# PDB_first.net
KiCad netlist of a schematic drawn in Altium Designer
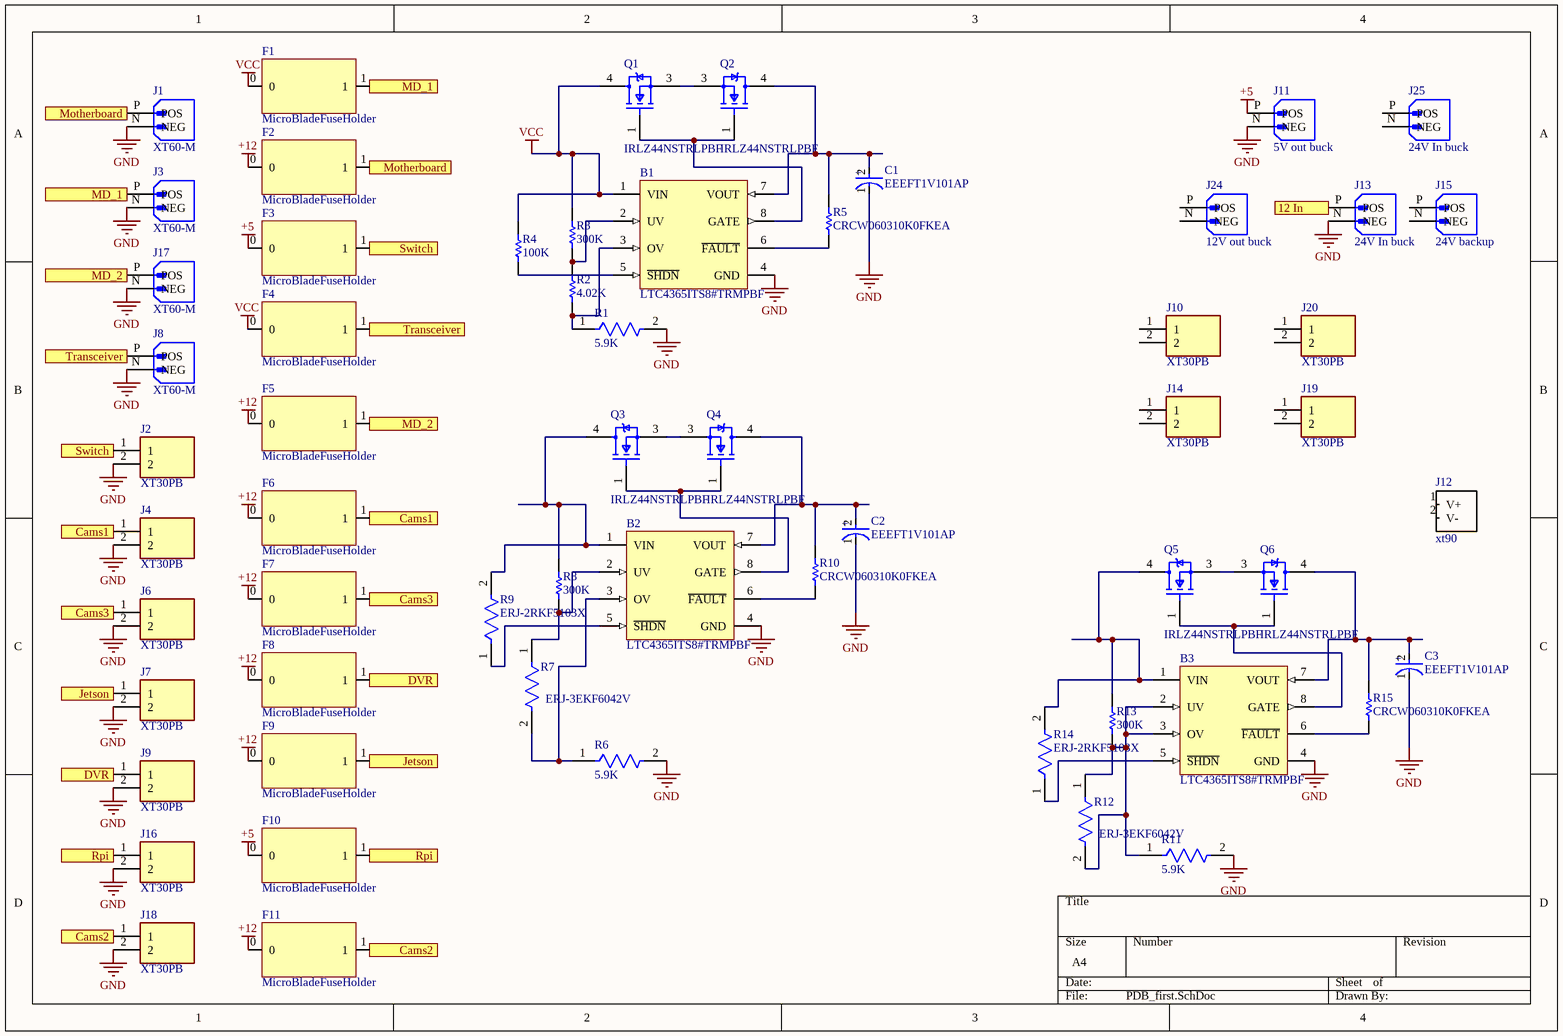
[diagram p0: PDB_first.SchDoc]

(export (version "E")
  (design (tool "Eeschema 10.0.6"))
  (components
    (comp (ref "B1")
      (value "LTC4365ITS8#TRMPBF")
      (footprint "LT-TS8-8-TSOT-23_V")
      (fields (field (name "MANUFACTURER") "Linear Technology"))
      (libsource (lib "Altium Content Vault") (part "LT-LTC4365-TS8-8"))
    )
    (comp (ref "B2")
      (value "LTC4365ITS8#TRMPBF")
      (footprint "LT-TS8-8-TSOT-23_V")
      (fields (field (name "MANUFACTURER") "Linear Technology"))
      (libsource (lib "Altium Content Vault") (part "LT-LTC4365-TS8-8"))
    )
    (comp (ref "B3")
      (value "LTC4365ITS8#TRMPBF")
      (footprint "LT-TS8-8-TSOT-23_V")
      (fields (field (name "MANUFACTURER") "Linear Technology"))
      (libsource (lib "Altium Content Vault") (part "LT-LTC4365-TS8-8"))
    )
    (comp (ref "C1")
      (value "EEEFT1V101AP")
      (footprint "FP-FTD-MFG")
      (description "CAP ALUM 100UF 20% 35V SMD")
      (fields (field (name "VOLTAGE") "35V") (field (name "TOLERANCE") "20%"))
      (libsource (lib "Altium Content Vault") (part "a00bbbee19879c290e62620ae7e47b1"))
    )
    (comp (ref "C2")
      (value "EEEFT1V101AP")
      (footprint "FP-FTD-MFG")
      (description "CAP ALUM 100UF 20% 35V SMD")
      (fields (field (name "VOLTAGE") "35V") (field (name "TOLERANCE") "20%"))
      (libsource (lib "Altium Content Vault") (part "a00bbbee19879c290e62620ae7e47b1"))
    )
    (comp (ref "C3")
      (value "EEEFT1V101AP")
      (footprint "FP-FTD-MFG")
      (description "CAP ALUM 100UF 20% 35V SMD")
      (fields (field (name "VOLTAGE") "35V") (field (name "TOLERANCE") "20%"))
      (libsource (lib "Altium Content Vault") (part "a00bbbee19879c290e62620ae7e47b1"))
    )
    (comp (ref "F1")
      (value "MicroBladeFuseHolder")
      (libsource (lib "MicroBladeFuse") (part "MicroBladeFuseHolder"))
    )
    (comp (ref "F2")
      (value "MicroBladeFuseHolder")
      (libsource (lib "MicroBladeFuse") (part "MicroBladeFuseHolder"))
    )
    (comp (ref "F3")
      (value "MicroBladeFuseHolder")
      (libsource (lib "MicroBladeFuse") (part "MicroBladeFuseHolder"))
    )
    (comp (ref "F4")
      (value "MicroBladeFuseHolder")
      (libsource (lib "MicroBladeFuse") (part "MicroBladeFuseHolder"))
    )
    (comp (ref "F5")
      (value "MicroBladeFuseHolder")
      (libsource (lib "MicroBladeFuse") (part "MicroBladeFuseHolder"))
    )
    (comp (ref "F6")
      (value "MicroBladeFuseHolder")
      (libsource (lib "MicroBladeFuse") (part "MicroBladeFuseHolder"))
    )
    (comp (ref "F7")
      (value "MicroBladeFuseHolder")
      (libsource (lib "MicroBladeFuse") (part "MicroBladeFuseHolder"))
    )
    (comp (ref "F8")
      (value "MicroBladeFuseHolder")
      (libsource (lib "MicroBladeFuse") (part "MicroBladeFuseHolder"))
    )
    (comp (ref "F9")
      (value "MicroBladeFuseHolder")
      (libsource (lib "MicroBladeFuse") (part "MicroBladeFuseHolder"))
    )
    (comp (ref "F10")
      (value "MicroBladeFuseHolder")
      (libsource (lib "MicroBladeFuse") (part "MicroBladeFuseHolder"))
    )
    (comp (ref "F11")
      (value "MicroBladeFuseHolder")
      (libsource (lib "MicroBladeFuse") (part "MicroBladeFuseHolder"))
    )
    (comp (ref "J1")
      (value "XT60-M")
      (footprint "AMASS_XT60-M")
      (description "Plug; DC supply; XT60; male; PIN: 2; for cable; soldered; 30A; 500V")
      (fields (field (name "MF") "AMASS"))
      (libsource (lib "XT60-M") (part "XT60-M"))
    )
    (comp (ref "J2")
      (value "XT30PB")
      (footprint "SamacSys:XT30PB")
      (description "Connector")
      (libsource (lib "SamacSys") (part "XT30PB"))
    )
    (comp (ref "J3")
      (value "XT60-M")
      (footprint "AMASS_XT60-M")
      (description "Plug; DC supply; XT60; male; PIN: 2; for cable; soldered; 30A; 500V")
      (fields (field (name "MF") "AMASS"))
      (libsource (lib "XT60-M") (part "XT60-M"))
    )
    (comp (ref "J4")
      (value "XT30PB")
      (footprint "SamacSys:XT30PB")
      (description "Connector")
      (libsource (lib "SamacSys") (part "XT30PB"))
    )
    (comp (ref "J6")
      (value "XT30PB")
      (footprint "SamacSys:XT30PB")
      (description "Connector")
      (libsource (lib "SamacSys") (part "XT30PB"))
    )
    (comp (ref "J7")
      (value "XT30PB")
      (footprint "SamacSys:XT30PB")
      (description "Connector")
      (libsource (lib "SamacSys") (part "XT30PB"))
    )
    (comp (ref "J8")
      (value "XT60-M")
      (footprint "AMASS_XT60-M")
      (description "Plug; DC supply; XT60; male; PIN: 2; for cable; soldered; 30A; 500V")
      (fields (field (name "MF") "AMASS"))
      (libsource (lib "XT60-M") (part "XT60-M"))
    )
    (comp (ref "J9")
      (value "XT30PB")
      (footprint "SamacSys:XT30PB")
      (description "Connector")
      (libsource (lib "SamacSys") (part "XT30PB"))
    )
    (comp (ref "J10")
      (value "XT30PB")
      (footprint "SamacSys:XT30PB")
      (description "Connector")
      (libsource (lib "SamacSys") (part "XT30PB"))
    )
    (comp (ref "J11")
      (value "5V out buck")
      (footprint "AMASS_XT60-M")
      (description "Plug; DC supply; XT60; male; PIN: 2; for cable; soldered; 30A; 500V")
      (fields (field (name "MP") "XT60-M") (field (name "MF") "AMASS"))
      (libsource (lib "XT60-M") (part "XT60-M"))
    )
    (comp (ref "J12") (value "xt90") (footprint "xt90") (libsource (lib "Schlib1") (part "xt90")))
    (comp (ref "J13")
      (value "24V In buck")
      (footprint "AMASS_XT60-M")
      (description "Plug; DC supply; XT60; male; PIN: 2; for cable; soldered; 30A; 500V")
      (fields (field (name "MP") "XT60-M") (field (name "MF") "AMASS"))
      (libsource (lib "XT60-M") (part "XT60-M"))
    )
    (comp (ref "J14")
      (value "XT30PB")
      (footprint "SamacSys:XT30PB")
      (description "Connector")
      (libsource (lib "SamacSys") (part "XT30PB"))
    )
    (comp (ref "J15")
      (value "24V backup")
      (footprint "AMASS_XT60-M")
      (fields (field (name "MF") "AMASS") (field (name "MP") "XT60-M"))
      (libsource (lib "XT60-M") (part "XT60-M"))
    )
    (comp (ref "J16")
      (value "XT30PB")
      (footprint "SamacSys:XT30PB")
      (description "Connector")
      (libsource (lib "SamacSys") (part "XT30PB"))
    )
    (comp (ref "J17")
      (value "XT60-M")
      (footprint "AMASS_XT60-M")
      (description "Plug; DC supply; XT60; male; PIN: 2; for cable; soldered; 30A; 500V")
      (fields (field (name "MF") "AMASS"))
      (libsource (lib "XT60-M") (part "XT60-M"))
    )
    (comp (ref "J18")
      (value "XT30PB")
      (footprint "SamacSys:XT30PB")
      (description "Connector")
      (libsource (lib "SamacSys") (part "XT30PB"))
    )
    (comp (ref "J19")
      (value "XT30PB")
      (footprint "SamacSys:XT30PB")
      (description "12V backup")
      (libsource (lib "SamacSys") (part "XT30PB"))
    )
    (comp (ref "J20")
      (value "XT30PB")
      (footprint "SamacSys:XT30PB")
      (description "24V backup")
      (libsource (lib "SamacSys") (part "XT30PB"))
    )
    (comp (ref "J24")
      (value "12V out buck")
      (footprint "AMASS_XT60-M")
      (description "Plug; DC supply; XT60; male; PIN: 2; for cable; soldered; 30A; 500V")
      (fields (field (name "MF") "AMASS") (field (name "MP") "XT60-M"))
      (libsource (lib "XT60-M") (part "XT60-M"))
    )
    (comp (ref "J25")
      (value "24V In buck")
      (footprint "AMASS_XT60-M")
      (description "Plug; DC supply; XT60; male; PIN: 2; for cable; soldered; 30A; 500V")
      (fields (field (name "MF") "AMASS") (field (name "MP") "XT60-M"))
      (libsource (lib "XT60-M") (part "XT60-M"))
    )
    (comp (ref "Q1")
      (value "IRLZ44NSTRLPBF")
      (footprint "FP-PG-TO263-3-MFG")
      (description "MOSFET N-CH 55V 47A D2PAK")
      (libsource (lib "Altium Content Vault") (part "cdf1c68f84cb049e5ebc85739c3fcf6"))
    )
    (comp (ref "Q2")
      (value "IRLZ44NSTRLPBF")
      (footprint "FP-PG-TO263-3-MFG")
      (description "MOSFET N-CH 55V 47A D2PAK")
      (libsource (lib "Altium Content Vault") (part "cdf1c68f84cb049e5ebc85739c3fcf6"))
    )
    (comp (ref "Q3")
      (value "IRLZ44NSTRLPBF")
      (footprint "FP-PG-TO263-3-MFG")
      (description "MOSFET N-CH 55V 47A D2PAK")
      (libsource (lib "Altium Content Vault") (part "cdf1c68f84cb049e5ebc85739c3fcf6"))
    )
    (comp (ref "Q4")
      (value "IRLZ44NSTRLPBF")
      (footprint "FP-PG-TO263-3-MFG")
      (description "MOSFET N-CH 55V 47A D2PAK")
      (libsource (lib "Altium Content Vault") (part "cdf1c68f84cb049e5ebc85739c3fcf6"))
    )
    (comp (ref "Q5")
      (value "IRLZ44NSTRLPBF")
      (footprint "FP-PG-TO263-3-MFG")
      (description "MOSFET N-CH 55V 47A D2PAK")
      (libsource (lib "Altium Content Vault") (part "cdf1c68f84cb049e5ebc85739c3fcf6"))
    )
    (comp (ref "Q6")
      (value "IRLZ44NSTRLPBF")
      (footprint "FP-PG-TO263-3-MFG")
      (description "MOSFET N-CH 55V 47A D2PAK")
      (libsource (lib "Altium Content Vault") (part "cdf1c68f84cb049e5ebc85739c3fcf6"))
    )
    (comp (ref "R1")
      (value "5.9K")
      (footprint "FP-ERJ2RK-IPC_A")
      (description "RES SMD 5.9K OHM 1% 1/10W 0402")
      (fields (field (name "TOLERANCE") "1%"))
      (libsource (lib "Altium Content Vault") (part "1029c3af85768c4190bb7ad29bc67b5"))
    )
    (comp (ref "R2")
      (value "4.02K")
      (footprint "RESC1608X55X30LL15T15")
      (fields (field (name "MANUFACTURER") "Panasonic") (field (name "PART NUMBER") "ERJ-3EKF4021V"))
      (libsource (lib "Altium Content Vault") (part "RES"))
    )
    (comp (ref "R3")
      (value "300K")
      (footprint "RESC2013X70X40ML20T20")
      (fields (field (name "PART NUMBER") "ERJ-6GEYJ304V") (field (name "MANUFACTURER") "Panasonic"))
      (libsource (lib "Altium Content Vault") (part "RES"))
    )
    (comp (ref "R4")
      (value "100K")
      (footprint "RESC1608X55X30ML15T15")
      (fields (field (name "PART NUMBER") "ERJ-3EKF1003V") (field (name "MANUFACTURER") "Panasonic"))
      (libsource (lib "Altium Content Vault") (part "RES"))
    )
    (comp (ref "R5")
      (value "CRCW060310K0FKEA")
      (footprint "RESC1609X50X30NL8T20")
      (description "Chip Resistor, 10 KOhm, +/- 1%, 100 mW, -55 to 155 degC, 0603 (1608 Metric), RoHS, Tape and Reel")
      (fields (field (name "MANUFACTURER") "Vishay Semiconductor"))
      (libsource (lib "Altium Content Vault") (part "RES-2"))
    )
    (comp (ref "R6")
      (value "5.9K")
      (footprint "FP-ERJ2RK-IPC_A")
      (description "RES SMD 5.9K OHM 1% 1/10W 0402")
      (fields (field (name "TOLERANCE") "1%"))
      (libsource (lib "Altium Content Vault") (part "1029c3af85768c4190bb7ad29bc67b5"))
    )
    (comp (ref "R7")
      (value "ERJ-3EKF6042V")
      (footprint "FP-ERJ3EK-MFG")
      (fields (field (name "TOLERANCE") "1%"))
      (libsource (lib "Altium Content Vault") (part "1029c3af85768c4190bb7ad29bc67b5"))
    )
    (comp (ref "R8")
      (value "300K")
      (footprint "RESC2013X70X40ML20T20")
      (fields (field (name "PART NUMBER") "ERJ-6GEYJ304V") (field (name "MANUFACTURER") "Panasonic"))
      (libsource (lib "Altium Content Vault") (part "RES"))
    )
    (comp (ref "R9")
      (value "ERJ-2RKF5103X")
      (footprint "FP-ERJ2RK-IPC_B")
      (description "RES SMD 510K OHM 1% 1/10W 0402")
      (fields (field (name "TOLERANCE") "1%"))
      (libsource (lib "Altium Content Vault") (part "1029c3af85768c4190bb7ad29bc67b5"))
    )
    (comp (ref "R10")
      (value "CRCW060310K0FKEA")
      (footprint "RESC1609X50X30NL8T20")
      (description "Chip Resistor, 10 KOhm, +/- 1%, 100 mW, -55 to 155 degC, 0603 (1608 Metric), RoHS, Tape and Reel")
      (fields (field (name "MANUFACTURER") "Vishay Semiconductor"))
      (libsource (lib "Altium Content Vault") (part "RES-2"))
    )
    (comp (ref "R11")
      (value "5.9K")
      (footprint "FP-ERJ2RK-IPC_A")
      (description "RES SMD 5.9K OHM 1% 1/10W 0402")
      (fields (field (name "TOLERANCE") "1%"))
      (libsource (lib "Altium Content Vault") (part "1029c3af85768c4190bb7ad29bc67b5"))
    )
    (comp (ref "R12")
      (value "ERJ-3EKF6042V")
      (footprint "FP-ERJ3EK-MFG")
      (fields (field (name "TOLERANCE") "1%"))
      (libsource (lib "Altium Content Vault") (part "1029c3af85768c4190bb7ad29bc67b5"))
    )
    (comp (ref "R13")
      (value "300K")
      (footprint "RESC2013X70X40ML20T20")
      (fields (field (name "PART NUMBER") "ERJ-6GEYJ304V") (field (name "MANUFACTURER") "Panasonic"))
      (libsource (lib "Altium Content Vault") (part "RES"))
    )
    (comp (ref "R14")
      (value "ERJ-2RKF5103X")
      (footprint "FP-ERJ2RK-IPC_B")
      (description "RES SMD 510K OHM 1% 1/10W 0402")
      (fields (field (name "TOLERANCE") "1%"))
      (libsource (lib "Altium Content Vault") (part "1029c3af85768c4190bb7ad29bc67b5"))
    )
    (comp (ref "R15")
      (value "CRCW060310K0FKEA")
      (footprint "RESC1609X50X30NL8T20")
      (description "Chip Resistor, 10 KOhm, +/- 1%, 100 mW, -55 to 155 degC, 0603 (1608 Metric), RoHS, Tape and Reel")
      (fields (field (name "MANUFACTURER") "Vishay Semiconductor"))
      (libsource (lib "Altium Content Vault") (part "RES-2"))
    )
  )
  (nets
    (net (code "1") (name "+5") (class "Default")
      (node (ref "F10") (pin "0") (pinfunction "0_0") (pintype "passive"))
      (node (ref "F3") (pin "0") (pinfunction "0_0") (pintype "passive"))
      (node (ref "J11") (pin "P") (pinfunction "POS_P") (pintype "passive"))
    )
    (net (code "2") (name "+12") (class "Default")
      (node (ref "F11") (pin "0") (pinfunction "0_0") (pintype "passive"))
      (node (ref "F2") (pin "0") (pinfunction "0_0") (pintype "passive"))
      (node (ref "F5") (pin "0") (pinfunction "0_0") (pintype "passive"))
      (node (ref "F6") (pin "0") (pinfunction "0_0") (pintype "passive"))
      (node (ref "F7") (pin "0") (pinfunction "0_0") (pintype "passive"))
      (node (ref "F8") (pin "0") (pinfunction "0_0") (pintype "passive"))
      (node (ref "F9") (pin "0") (pinfunction "0_0") (pintype "passive"))
    )
    (net (code "3") (name "/12 In") (class "Default")
      (node (ref "J13") (pin "P") (pinfunction "POS_P") (pintype "passive"))
    )
    (net (code "4") (name "/Cams1") (class "Default")
      (node (ref "F6") (pin "1") (pinfunction "1_1") (pintype "passive"))
      (node (ref "J4") (pin "1") (pinfunction "1_1") (pintype "passive"))
    )
    (net (code "5") (name "/Cams2") (class "Default")
      (node (ref "F11") (pin "1") (pinfunction "1_1") (pintype "passive"))
      (node (ref "J18") (pin "1") (pinfunction "1_1") (pintype "passive"))
    )
    (net (code "6") (name "/Cams3") (class "Default")
      (node (ref "F7") (pin "1") (pinfunction "1_1") (pintype "passive"))
      (node (ref "J6") (pin "1") (pinfunction "1_1") (pintype "passive"))
    )
    (net (code "7") (name "/DVR") (class "Default")
      (node (ref "F8") (pin "1") (pinfunction "1_1") (pintype "passive"))
      (node (ref "J9") (pin "1") (pinfunction "1_1") (pintype "passive"))
    )
    (net (code "8") (name "/Jetson") (class "Default")
      (node (ref "F9") (pin "1") (pinfunction "1_1") (pintype "passive"))
      (node (ref "J7") (pin "1") (pinfunction "1_1") (pintype "passive"))
    )
    (net (code "9") (name "/MD_1") (class "Default")
      (node (ref "F1") (pin "1") (pinfunction "1_1") (pintype "passive"))
      (node (ref "J3") (pin "P") (pinfunction "POS_P") (pintype "passive"))
    )
    (net (code "10") (name "/MD_2") (class "Default")
      (node (ref "F5") (pin "1") (pinfunction "1_1") (pintype "passive"))
      (node (ref "J17") (pin "P") (pinfunction "POS_P") (pintype "passive"))
    )
    (net (code "11") (name "/Motherboard") (class "Default")
      (node (ref "F2") (pin "1") (pinfunction "1_1") (pintype "passive"))
      (node (ref "J1") (pin "P") (pinfunction "POS_P") (pintype "passive"))
    )
    (net (code "12") (name "/Rpi") (class "Default")
      (node (ref "F10") (pin "1") (pinfunction "1_1") (pintype "passive"))
      (node (ref "J16") (pin "1") (pinfunction "1_1") (pintype "passive"))
    )
    (net (code "13") (name "/Switch") (class "Default")
      (node (ref "F3") (pin "1") (pinfunction "1_1") (pintype "passive"))
      (node (ref "J2") (pin "1") (pinfunction "1_1") (pintype "passive"))
    )
    (net (code "14") (name "/Transceiver") (class "Default")
      (node (ref "F4") (pin "1") (pinfunction "1_1") (pintype "passive"))
      (node (ref "J8") (pin "P") (pinfunction "POS_P") (pintype "passive"))
    )
    (net (code "15") (name "GND") (class "Default")
      (node (ref "B1") (pin "4") (pinfunction "GND_4") (pintype "power_in"))
      (node (ref "B2") (pin "4") (pinfunction "GND_4") (pintype "power_in"))
      (node (ref "B3") (pin "4") (pinfunction "GND_4") (pintype "power_in"))
      (node (ref "C1") (pin "1") (pinfunction "C_1") (pintype "passive"))
      (node (ref "C2") (pin "1") (pinfunction "C_1") (pintype "passive"))
      (node (ref "C3") (pin "1") (pinfunction "C_1") (pintype "passive"))
      (node (ref "J1") (pin "N") (pinfunction "NEG_N") (pintype "passive"))
      (node (ref "J11") (pin "N") (pinfunction "NEG_N") (pintype "passive"))
      (node (ref "J13") (pin "N") (pinfunction "NEG_N") (pintype "passive"))
      (node (ref "J16") (pin "2") (pinfunction "2_2") (pintype "passive"))
      (node (ref "J17") (pin "N") (pinfunction "NEG_N") (pintype "passive"))
      (node (ref "J18") (pin "2") (pinfunction "2_2") (pintype "passive"))
      (node (ref "J2") (pin "2") (pinfunction "2_2") (pintype "passive"))
      (node (ref "J3") (pin "N") (pinfunction "NEG_N") (pintype "passive"))
      (node (ref "J4") (pin "2") (pinfunction "2_2") (pintype "passive"))
      (node (ref "J6") (pin "2") (pinfunction "2_2") (pintype "passive"))
      (node (ref "J7") (pin "2") (pinfunction "2_2") (pintype "passive"))
      (node (ref "J8") (pin "N") (pinfunction "NEG_N") (pintype "passive"))
      (node (ref "J9") (pin "2") (pinfunction "2_2") (pintype "passive"))
      (node (ref "R1") (pin "2") (pinfunction "2_2") (pintype "passive"))
      (node (ref "R11") (pin "2") (pinfunction "2_2") (pintype "passive"))
      (node (ref "R6") (pin "2") (pinfunction "2_2") (pintype "passive"))
    )
    (net (code "16") (name "Net-(B1-GATE)") (class "Default")
      (node (ref "B1") (pin "8") (pinfunction "GATE_8") (pintype "output"))
      (node (ref "Q1") (pin "1") (pinfunction "G_1") (pintype "passive"))
      (node (ref "Q2") (pin "1") (pinfunction "G_1") (pintype "passive"))
    )
    (net (code "17") (name "Net-(B1-OV)") (class "Default")
      (node (ref "B1") (pin "3") (pinfunction "OV_3") (pintype "input"))
      (node (ref "R1") (pin "1") (pinfunction "1_1") (pintype "passive"))
      (node (ref "R2") (pin "1") (pinfunction "1_1") (pintype "passive"))
    )
    (net (code "18") (name "Net-(B1-UV)") (class "Default")
      (node (ref "B1") (pin "2") (pinfunction "UV_2") (pintype "input"))
      (node (ref "R2") (pin "2") (pinfunction "2_2") (pintype "passive"))
      (node (ref "R3") (pin "1") (pinfunction "1_1") (pintype "passive"))
    )
    (net (code "19") (name "Net-(B1-VOUT)") (class "Default")
      (node (ref "B1") (pin "7") (pinfunction "VOUT_7") (pintype "input"))
      (node (ref "C1") (pin "2") (pinfunction "A_2") (pintype "passive"))
      (node (ref "Q2") (pin "4") (pinfunction "D_4") (pintype "passive"))
      (node (ref "R5") (pin "2") (pinfunction "2_2") (pintype "passive"))
    )
    (net (code "20") (name "Net-(B1-~{FAULT})") (class "Default")
      (node (ref "B1") (pin "6") (pinfunction "~{FAULT}_6") (pintype "open_collector"))
      (node (ref "R5") (pin "1") (pinfunction "1_1") (pintype "passive"))
    )
    (net (code "21") (name "Net-(B1-~{SHDN})") (class "Default")
      (node (ref "B1") (pin "5") (pinfunction "~{SHDN}_5") (pintype "input"))
      (node (ref "R4") (pin "1") (pinfunction "1_1") (pintype "passive"))
    )
    (net (code "22") (name "Net-(B2-GATE)") (class "Default")
      (node (ref "B2") (pin "8") (pinfunction "GATE_8") (pintype "output"))
      (node (ref "Q3") (pin "1") (pinfunction "G_1") (pintype "passive"))
      (node (ref "Q4") (pin "1") (pinfunction "G_1") (pintype "passive"))
    )
    (net (code "23") (name "Net-(B2-OV)") (class "Default")
      (node (ref "B2") (pin "3") (pinfunction "OV_3") (pintype "input"))
      (node (ref "R6") (pin "1") (pinfunction "1_1") (pintype "passive"))
      (node (ref "R7") (pin "2") (pinfunction "2_2") (pintype "passive"))
    )
    (net (code "24") (name "Net-(B2-UV)") (class "Default")
      (node (ref "B2") (pin "2") (pinfunction "UV_2") (pintype "input"))
      (node (ref "R7") (pin "1") (pinfunction "1_1") (pintype "passive"))
      (node (ref "R8") (pin "1") (pinfunction "1_1") (pintype "passive"))
    )
    (net (code "25") (name "Net-(B2-VIN)") (class "Default")
      (node (ref "B2") (pin "1") (pinfunction "VIN_1") (pintype "power_in"))
      (node (ref "Q3") (pin "4") (pinfunction "D_4") (pintype "passive"))
      (node (ref "R8") (pin "2") (pinfunction "2_2") (pintype "passive"))
      (node (ref "R9") (pin "2") (pinfunction "2_2") (pintype "passive"))
    )
    (net (code "26") (name "Net-(B2-VOUT)") (class "Default")
      (node (ref "B2") (pin "7") (pinfunction "VOUT_7") (pintype "input"))
      (node (ref "C2") (pin "2") (pinfunction "A_2") (pintype "passive"))
      (node (ref "Q4") (pin "4") (pinfunction "D_4") (pintype "passive"))
      (node (ref "R10") (pin "2") (pinfunction "2_2") (pintype "passive"))
    )
    (net (code "27") (name "Net-(B2-~{FAULT})") (class "Default")
      (node (ref "B2") (pin "6") (pinfunction "~{FAULT}_6") (pintype "open_collector"))
      (node (ref "R10") (pin "1") (pinfunction "1_1") (pintype "passive"))
    )
    (net (code "28") (name "Net-(B2-~{SHDN})") (class "Default")
      (node (ref "B2") (pin "5") (pinfunction "~{SHDN}_5") (pintype "input"))
      (node (ref "R9") (pin "1") (pinfunction "1_1") (pintype "passive"))
    )
    (net (code "29") (name "Net-(B3-GATE)") (class "Default")
      (node (ref "B3") (pin "8") (pinfunction "GATE_8") (pintype "output"))
      (node (ref "Q5") (pin "1") (pinfunction "G_1") (pintype "passive"))
      (node (ref "Q6") (pin "1") (pinfunction "G_1") (pintype "passive"))
    )
    (net (code "30") (name "Net-(B3-OV)") (class "Default")
      (node (ref "B3") (pin "2") (pinfunction "UV_2") (pintype "input"))
      (node (ref "B3") (pin "3") (pinfunction "OV_3") (pintype "input"))
      (node (ref "R11") (pin "1") (pinfunction "1_1") (pintype "passive"))
      (node (ref "R12") (pin "1") (pinfunction "1_1") (pintype "passive"))
      (node (ref "R12") (pin "2") (pinfunction "2_2") (pintype "passive"))
      (node (ref "R13") (pin "1") (pinfunction "1_1") (pintype "passive"))
    )
    (net (code "31") (name "Net-(B3-VIN)") (class "Default")
      (node (ref "B3") (pin "1") (pinfunction "VIN_1") (pintype "power_in"))
      (node (ref "Q5") (pin "4") (pinfunction "D_4") (pintype "passive"))
      (node (ref "R13") (pin "2") (pinfunction "2_2") (pintype "passive"))
      (node (ref "R14") (pin "2") (pinfunction "2_2") (pintype "passive"))
    )
    (net (code "32") (name "Net-(B3-VOUT)") (class "Default")
      (node (ref "B3") (pin "7") (pinfunction "VOUT_7") (pintype "input"))
      (node (ref "C3") (pin "2") (pinfunction "A_2") (pintype "passive"))
      (node (ref "Q6") (pin "4") (pinfunction "D_4") (pintype "passive"))
      (node (ref "R15") (pin "2") (pinfunction "2_2") (pintype "passive"))
    )
    (net (code "33") (name "Net-(B3-~{FAULT})") (class "Default")
      (node (ref "B3") (pin "6") (pinfunction "~{FAULT}_6") (pintype "open_collector"))
      (node (ref "R15") (pin "1") (pinfunction "1_1") (pintype "passive"))
    )
    (net (code "34") (name "Net-(B3-~{SHDN})") (class "Default")
      (node (ref "B3") (pin "5") (pinfunction "~{SHDN}_5") (pintype "input"))
      (node (ref "R14") (pin "1") (pinfunction "1_1") (pintype "passive"))
    )
    (net (code "35") (name "Net-(Q1-S)") (class "Default")
      (node (ref "Q1") (pin "3") (pinfunction "S_3") (pintype "passive"))
      (node (ref "Q2") (pin "3") (pinfunction "S_3") (pintype "passive"))
    )
    (net (code "36") (name "Net-(Q3-S)") (class "Default")
      (node (ref "Q3") (pin "3") (pinfunction "S_3") (pintype "passive"))
      (node (ref "Q4") (pin "3") (pinfunction "S_3") (pintype "passive"))
    )
    (net (code "37") (name "Net-(Q5-S)") (class "Default")
      (node (ref "Q5") (pin "3") (pinfunction "S_3") (pintype "passive"))
      (node (ref "Q6") (pin "3") (pinfunction "S_3") (pintype "passive"))
    )
    (net (code "38") (name "VCC") (class "Default")
      (node (ref "B1") (pin "1") (pinfunction "VIN_1") (pintype "power_in"))
      (node (ref "F1") (pin "0") (pinfunction "0_0") (pintype "passive"))
      (node (ref "F4") (pin "0") (pinfunction "0_0") (pintype "passive"))
      (node (ref "Q1") (pin "4") (pinfunction "D_4") (pintype "passive"))
      (node (ref "R3") (pin "2") (pinfunction "2_2") (pintype "passive"))
      (node (ref "R4") (pin "2") (pinfunction "2_2") (pintype "passive"))
    )
    (net (code "39") (name "unconnected-(J10-Pad1)") (class "Default")
      (node (ref "J10") (pin "1") (pinfunction "1_1") (pintype "passive"))
    )
    (net (code "40") (name "unconnected-(J10-Pad2)") (class "Default")
      (node (ref "J10") (pin "2") (pinfunction "2_2") (pintype "passive"))
    )
    (net (code "41") (name "unconnected-(J12-V+-Pad1)") (class "Default")
      (node (ref "J12") (pin "1") (pinfunction "V+_1") (pintype "passive"))
    )
    (net (code "42") (name "unconnected-(J12-V--Pad2)") (class "Default")
      (node (ref "J12") (pin "2") (pinfunction "V-_2") (pintype "passive"))
    )
    (net (code "43") (name "unconnected-(J14-Pad1)") (class "Default")
      (node (ref "J14") (pin "1") (pinfunction "1_1") (pintype "passive"))
    )
    (net (code "44") (name "unconnected-(J14-Pad2)") (class "Default")
      (node (ref "J14") (pin "2") (pinfunction "2_2") (pintype "passive"))
    )
    (net (code "45") (name "unconnected-(J15-NEG-PadN)") (class "Default")
      (node (ref "J15") (pin "N") (pinfunction "NEG_N") (pintype "passive"))
    )
    (net (code "46") (name "unconnected-(J15-POS-PadP)") (class "Default")
      (node (ref "J15") (pin "P") (pinfunction "POS_P") (pintype "passive"))
    )
    (net (code "47") (name "unconnected-(J19-Pad1)") (class "Default")
      (node (ref "J19") (pin "1") (pinfunction "1_1") (pintype "passive"))
    )
    (net (code "48") (name "unconnected-(J19-Pad2)") (class "Default")
      (node (ref "J19") (pin "2") (pinfunction "2_2") (pintype "passive"))
    )
    (net (code "49") (name "unconnected-(J20-Pad1)") (class "Default")
      (node (ref "J20") (pin "1") (pinfunction "1_1") (pintype "passive"))
    )
    (net (code "50") (name "unconnected-(J20-Pad2)") (class "Default")
      (node (ref "J20") (pin "2") (pinfunction "2_2") (pintype "passive"))
    )
    (net (code "51") (name "unconnected-(J24-NEG-PadN)") (class "Default")
      (node (ref "J24") (pin "N") (pinfunction "NEG_N") (pintype "passive"))
    )
    (net (code "52") (name "unconnected-(J24-POS-PadP)") (class "Default")
      (node (ref "J24") (pin "P") (pinfunction "POS_P") (pintype "passive"))
    )
    (net (code "53") (name "unconnected-(J25-NEG-PadN)") (class "Default")
      (node (ref "J25") (pin "N") (pinfunction "NEG_N") (pintype "passive"))
    )
    (net (code "54") (name "unconnected-(J25-POS-PadP)") (class "Default")
      (node (ref "J25") (pin "P") (pinfunction "POS_P") (pintype "passive"))
    )
  )
)
